# rx08-ulrich.net
KiCad netlist of a schematic drawn in EAGLE
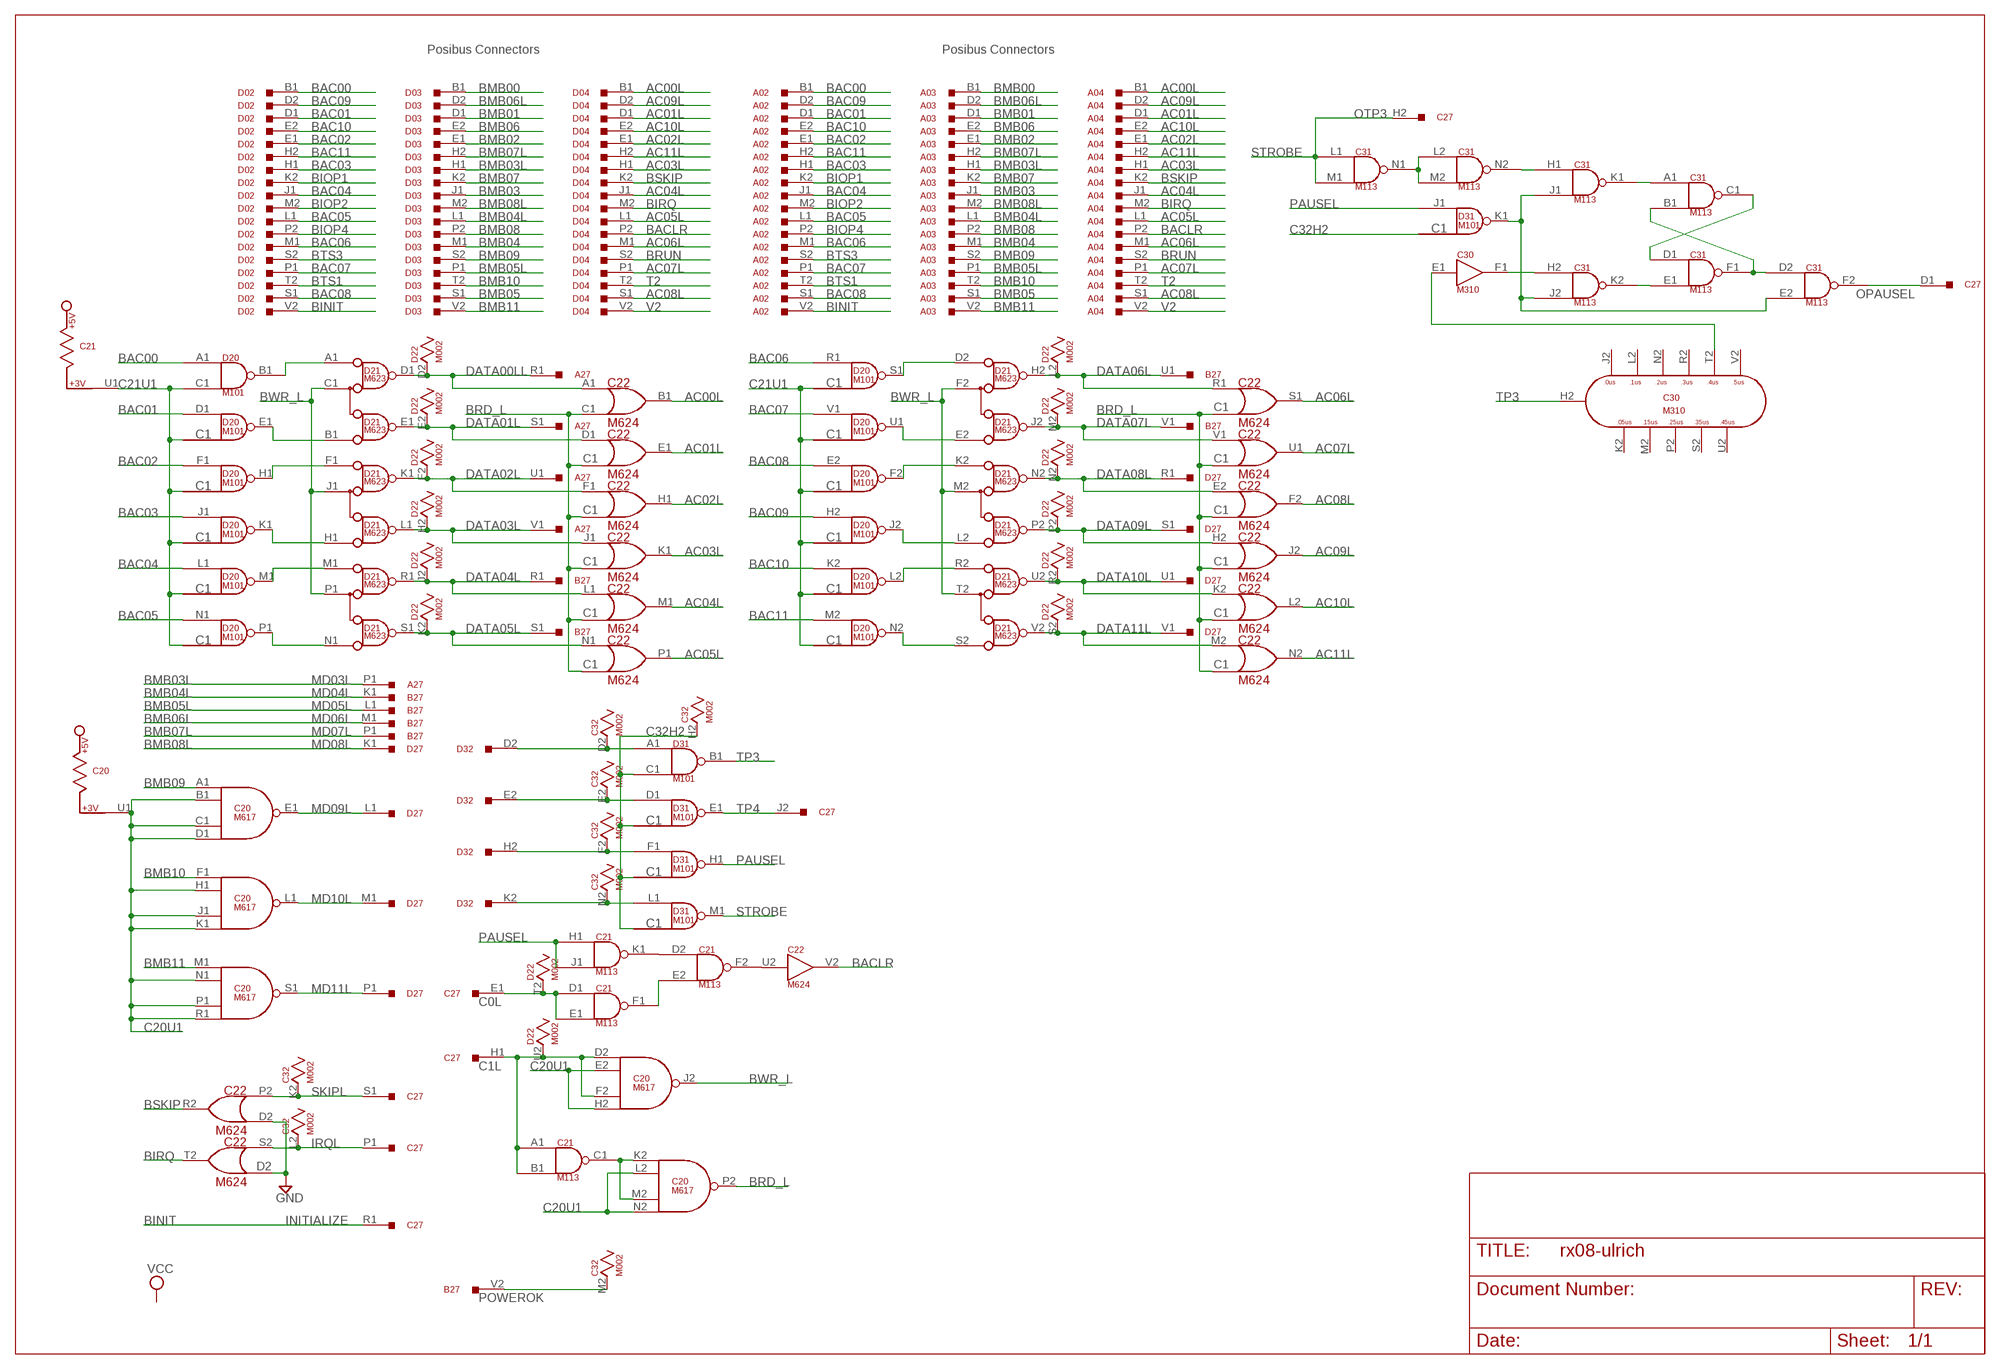
[diagram p0: schematic, sheet 1]

(export (version "E")
  (design (tool "Eeschema 10.0.6"))
  (components
    (comp (ref "A02")
      (value "M903")
      (footprint "eagle-import:H807")
      (libsource (lib "eagle-import") (part "M903"))
    )
    (comp (ref "A03")
      (value "M903")
      (footprint "eagle-import:H807")
      (libsource (lib "eagle-import") (part "M903"))
    )
    (comp (ref "A04")
      (value "M903")
      (footprint "eagle-import:H807")
      (libsource (lib "eagle-import") (part "M903"))
    )
    (comp (ref "A27")
      (value "M916")
      (footprint "eagle-import:H807")
      (libsource (lib "eagle-import") (part "M916"))
    )
    (comp (ref "B27")
      (value "M916")
      (footprint "eagle-import:H807")
      (libsource (lib "eagle-import") (part "M916"))
    )
    (comp (ref "C20")
      (value "M617")
      (footprint "eagle-import:H807")
      (libsource (lib "eagle-import") (part "M617"))
    )
    (comp (ref "C21")
      (value "M113")
      (footprint "eagle-import:H807")
      (libsource (lib "eagle-import") (part "M113"))
    )
    (comp (ref "C22")
      (value "M624")
      (footprint "eagle-import:H807")
      (libsource (lib "eagle-import") (part "M624"))
    )
    (comp (ref "C27")
      (value "M916")
      (footprint "eagle-import:H807")
      (libsource (lib "eagle-import") (part "M916"))
    )
    (comp (ref "C30")
      (value "M310")
      (footprint "eagle-import:H807")
      (libsource (lib "eagle-import") (part "M310"))
    )
    (comp (ref "C31")
      (value "M113")
      (footprint "eagle-import:H807")
      (libsource (lib "eagle-import") (part "M113"))
    )
    (comp (ref "C32")
      (value "M002")
      (footprint "eagle-import:H807")
      (libsource (lib "eagle-import") (part "M002"))
    )
    (comp (ref "D02")
      (value "M903")
      (footprint "eagle-import:H807")
      (libsource (lib "eagle-import") (part "M903"))
    )
    (comp (ref "D03")
      (value "M903")
      (footprint "eagle-import:H807")
      (libsource (lib "eagle-import") (part "M903"))
    )
    (comp (ref "D04")
      (value "M903")
      (footprint "eagle-import:H807")
      (libsource (lib "eagle-import") (part "M903"))
    )
    (comp (ref "D20")
      (value "M101")
      (footprint "eagle-import:H807")
      (libsource (lib "eagle-import") (part "M101"))
    )
    (comp (ref "D21")
      (value "M623")
      (footprint "eagle-import:H807")
      (libsource (lib "eagle-import") (part "M623"))
    )
    (comp (ref "D22")
      (value "M002")
      (footprint "eagle-import:H807")
      (libsource (lib "eagle-import") (part "M002"))
    )
    (comp (ref "D27")
      (value "M916")
      (footprint "eagle-import:H807")
      (libsource (lib "eagle-import") (part "M916"))
    )
    (comp (ref "D31")
      (value "M101")
      (footprint "eagle-import:H807")
      (libsource (lib "eagle-import") (part "M101"))
    )
    (comp (ref "D32")
      (value "M903")
      (footprint "eagle-import:H807")
      (libsource (lib "eagle-import") (part "M903"))
    )
  )
  (nets
    (net (code "1") (name "/AC00L") (class "Default")
      (node (ref "A04") (pin "B1") (pinfunction "P$2_B1") (pintype "bidirectional"))
      (node (ref "C22") (pin "B1") (pinfunction "OUT_B1") (pintype "output"))
      (node (ref "D04") (pin "B1") (pinfunction "P$2_B1") (pintype "bidirectional"))
    )
    (net (code "2") (name "/AC01L") (class "Default")
      (node (ref "A04") (pin "D1") (pinfunction "P$2_D1") (pintype "bidirectional"))
      (node (ref "C22") (pin "E1") (pinfunction "OUT_E1") (pintype "output"))
      (node (ref "D04") (pin "D1") (pinfunction "P$2_D1") (pintype "bidirectional"))
    )
    (net (code "3") (name "/AC02L") (class "Default")
      (node (ref "A04") (pin "E1") (pinfunction "P$2_E1") (pintype "bidirectional"))
      (node (ref "C22") (pin "H1") (pinfunction "OUT_H1") (pintype "output"))
      (node (ref "D04") (pin "E1") (pinfunction "P$2_E1") (pintype "bidirectional"))
    )
    (net (code "4") (name "/AC03L") (class "Default")
      (node (ref "A04") (pin "H1") (pinfunction "P$2_H1") (pintype "bidirectional"))
      (node (ref "C22") (pin "K1") (pinfunction "OUT_K1") (pintype "output"))
      (node (ref "D04") (pin "H1") (pinfunction "P$2_H1") (pintype "bidirectional"))
    )
    (net (code "5") (name "/AC04L") (class "Default")
      (node (ref "A04") (pin "J1") (pinfunction "P$2_J1") (pintype "bidirectional"))
      (node (ref "C22") (pin "M1") (pinfunction "OUT_M1") (pintype "output"))
      (node (ref "D04") (pin "J1") (pinfunction "P$2_J1") (pintype "bidirectional"))
    )
    (net (code "6") (name "/AC05L") (class "Default")
      (node (ref "A04") (pin "L1") (pinfunction "P$2_L1") (pintype "bidirectional"))
      (node (ref "C22") (pin "P1") (pinfunction "OUT_P1") (pintype "output"))
      (node (ref "D04") (pin "L1") (pinfunction "P$2_L1") (pintype "bidirectional"))
    )
    (net (code "7") (name "/AC06L") (class "Default")
      (node (ref "A04") (pin "M1") (pinfunction "P$2_M1") (pintype "bidirectional"))
      (node (ref "C22") (pin "S1") (pinfunction "OUT_S1") (pintype "output"))
      (node (ref "D04") (pin "M1") (pinfunction "P$2_M1") (pintype "bidirectional"))
    )
    (net (code "8") (name "/AC07L") (class "Default")
      (node (ref "A04") (pin "P1") (pinfunction "P$2_P1") (pintype "bidirectional"))
      (node (ref "C22") (pin "U1") (pinfunction "OUT_U1") (pintype "output"))
      (node (ref "D04") (pin "P1") (pinfunction "P$2_P1") (pintype "bidirectional"))
    )
    (net (code "9") (name "/AC08L") (class "Default")
      (node (ref "A04") (pin "S1") (pinfunction "P$2_S1") (pintype "bidirectional"))
      (node (ref "C22") (pin "F2") (pinfunction "OUT_F2") (pintype "output"))
      (node (ref "D04") (pin "S1") (pinfunction "P$2_S1") (pintype "bidirectional"))
    )
    (net (code "10") (name "/AC09L") (class "Default")
      (node (ref "A04") (pin "D2") (pinfunction "P$2_D2") (pintype "bidirectional"))
      (node (ref "C22") (pin "J2") (pinfunction "OUT_J2") (pintype "output"))
      (node (ref "D04") (pin "D2") (pinfunction "P$2_D2") (pintype "bidirectional"))
    )
    (net (code "11") (name "/AC10L") (class "Default")
      (node (ref "A04") (pin "E2") (pinfunction "P$2_E2") (pintype "bidirectional"))
      (node (ref "C22") (pin "L2") (pinfunction "OUT_L2") (pintype "output"))
      (node (ref "D04") (pin "E2") (pinfunction "P$2_E2") (pintype "bidirectional"))
    )
    (net (code "12") (name "/AC11L") (class "Default")
      (node (ref "A04") (pin "H2") (pinfunction "P$2_H2") (pintype "bidirectional"))
      (node (ref "C22") (pin "N2") (pinfunction "OUT_N2") (pintype "output"))
      (node (ref "D04") (pin "H2") (pinfunction "P$2_H2") (pintype "bidirectional"))
    )
    (net (code "13") (name "/BAC00") (class "Default")
      (node (ref "A02") (pin "B1") (pinfunction "P$2_B1") (pintype "bidirectional"))
      (node (ref "D02") (pin "B1") (pinfunction "P$2_B1") (pintype "bidirectional"))
      (node (ref "D20") (pin "A1") (pinfunction "IN1_A1") (pintype "input"))
    )
    (net (code "14") (name "/BAC01") (class "Default")
      (node (ref "A02") (pin "D1") (pinfunction "P$2_D1") (pintype "bidirectional"))
      (node (ref "D02") (pin "D1") (pinfunction "P$2_D1") (pintype "bidirectional"))
      (node (ref "D20") (pin "D1") (pinfunction "IN_D1") (pintype "input"))
    )
    (net (code "15") (name "/BAC02") (class "Default")
      (node (ref "A02") (pin "E1") (pinfunction "P$2_E1") (pintype "bidirectional"))
      (node (ref "D02") (pin "E1") (pinfunction "P$2_E1") (pintype "bidirectional"))
      (node (ref "D20") (pin "F1") (pinfunction "IN_F1") (pintype "input"))
    )
    (net (code "16") (name "/BAC03") (class "Default")
      (node (ref "A02") (pin "H1") (pinfunction "P$2_H1") (pintype "bidirectional"))
      (node (ref "D02") (pin "H1") (pinfunction "P$2_H1") (pintype "bidirectional"))
      (node (ref "D20") (pin "J1") (pinfunction "IN_J1") (pintype "input"))
    )
    (net (code "17") (name "/BAC04") (class "Default")
      (node (ref "A02") (pin "J1") (pinfunction "P$2_J1") (pintype "bidirectional"))
      (node (ref "D02") (pin "J1") (pinfunction "P$2_J1") (pintype "bidirectional"))
      (node (ref "D20") (pin "L1") (pinfunction "IN_L1") (pintype "input"))
    )
    (net (code "18") (name "/BAC05") (class "Default")
      (node (ref "A02") (pin "L1") (pinfunction "P$2_L1") (pintype "bidirectional"))
      (node (ref "D02") (pin "L1") (pinfunction "P$2_L1") (pintype "bidirectional"))
      (node (ref "D20") (pin "N1") (pinfunction "IN_N1") (pintype "input"))
    )
    (net (code "19") (name "/BAC06") (class "Default")
      (node (ref "A02") (pin "M1") (pinfunction "P$2_M1") (pintype "bidirectional"))
      (node (ref "D02") (pin "M1") (pinfunction "P$2_M1") (pintype "bidirectional"))
      (node (ref "D20") (pin "R1") (pinfunction "IN_R1") (pintype "input"))
    )
    (net (code "20") (name "/BAC07") (class "Default")
      (node (ref "A02") (pin "P1") (pinfunction "P$2_P1") (pintype "bidirectional"))
      (node (ref "D02") (pin "P1") (pinfunction "P$2_P1") (pintype "bidirectional"))
      (node (ref "D20") (pin "V1") (pinfunction "IN_V1") (pintype "input"))
    )
    (net (code "21") (name "/BAC08") (class "Default")
      (node (ref "A02") (pin "S1") (pinfunction "P$2_S1") (pintype "bidirectional"))
      (node (ref "D02") (pin "S1") (pinfunction "P$2_S1") (pintype "bidirectional"))
      (node (ref "D20") (pin "E2") (pinfunction "IN_E2") (pintype "input"))
    )
    (net (code "22") (name "/BAC09") (class "Default")
      (node (ref "A02") (pin "D2") (pinfunction "P$2_D2") (pintype "bidirectional"))
      (node (ref "D02") (pin "D2") (pinfunction "P$2_D2") (pintype "bidirectional"))
      (node (ref "D20") (pin "H2") (pinfunction "IN_H2") (pintype "input"))
    )
    (net (code "23") (name "/BAC10") (class "Default")
      (node (ref "A02") (pin "E2") (pinfunction "P$2_E2") (pintype "bidirectional"))
      (node (ref "D02") (pin "E2") (pinfunction "P$2_E2") (pintype "bidirectional"))
      (node (ref "D20") (pin "K2") (pinfunction "IN_K2") (pintype "input"))
    )
    (net (code "24") (name "/BAC11") (class "Default")
      (node (ref "A02") (pin "H2") (pinfunction "P$2_H2") (pintype "bidirectional"))
      (node (ref "D02") (pin "H2") (pinfunction "P$2_H2") (pintype "bidirectional"))
      (node (ref "D20") (pin "M2") (pinfunction "IN_M2") (pintype "input"))
    )
    (net (code "25") (name "/BACLR") (class "Default")
      (node (ref "A04") (pin "P2") (pinfunction "P$2_P2") (pintype "bidirectional"))
      (node (ref "C22") (pin "V2") (pinfunction "OUT_V2") (pintype "output"))
      (node (ref "D04") (pin "P2") (pinfunction "P$2_P2") (pintype "bidirectional"))
    )
    (net (code "26") (name "/BINIT") (class "Default")
      (node (ref "A02") (pin "V2") (pinfunction "P$2_V2") (pintype "bidirectional"))
      (node (ref "C27") (pin "R1") (pinfunction "P$2_R1") (pintype "bidirectional"))
      (node (ref "D02") (pin "V2") (pinfunction "P$2_V2") (pintype "bidirectional"))
    )
    (net (code "27") (name "/BIOP1") (class "Default")
      (node (ref "A02") (pin "K2") (pinfunction "P$2_K2") (pintype "bidirectional"))
      (node (ref "D02") (pin "K2") (pinfunction "P$2_K2") (pintype "bidirectional"))
    )
    (net (code "28") (name "/BIOP2") (class "Default")
      (node (ref "A02") (pin "M2") (pinfunction "P$2_M2") (pintype "bidirectional"))
      (node (ref "D02") (pin "M2") (pinfunction "P$2_M2") (pintype "bidirectional"))
    )
    (net (code "29") (name "/BIOP4") (class "Default")
      (node (ref "A02") (pin "P2") (pinfunction "P$2_P2") (pintype "bidirectional"))
      (node (ref "D02") (pin "P2") (pinfunction "P$2_P2") (pintype "bidirectional"))
    )
    (net (code "30") (name "/BIRQ") (class "Default")
      (node (ref "A04") (pin "M2") (pinfunction "P$2_M2") (pintype "bidirectional"))
      (node (ref "C22") (pin "T2") (pinfunction "OUT_T2") (pintype "output"))
      (node (ref "D04") (pin "M2") (pinfunction "P$2_M2") (pintype "bidirectional"))
    )
    (net (code "31") (name "/BMB00") (class "Default")
      (node (ref "A03") (pin "B1") (pinfunction "P$2_B1") (pintype "bidirectional"))
      (node (ref "D03") (pin "B1") (pinfunction "P$2_B1") (pintype "bidirectional"))
    )
    (net (code "32") (name "/BMB01") (class "Default")
      (node (ref "A03") (pin "D1") (pinfunction "P$2_D1") (pintype "bidirectional"))
      (node (ref "D03") (pin "D1") (pinfunction "P$2_D1") (pintype "bidirectional"))
    )
    (net (code "33") (name "/BMB02") (class "Default")
      (node (ref "A03") (pin "E1") (pinfunction "P$2_E1") (pintype "bidirectional"))
      (node (ref "D03") (pin "E1") (pinfunction "P$2_E1") (pintype "bidirectional"))
    )
    (net (code "34") (name "/BMB03") (class "Default")
      (node (ref "A03") (pin "J1") (pinfunction "P$2_J1") (pintype "bidirectional"))
      (node (ref "D03") (pin "J1") (pinfunction "P$2_J1") (pintype "bidirectional"))
    )
    (net (code "35") (name "/BMB03L") (class "Default")
      (node (ref "A03") (pin "H1") (pinfunction "P$2_H1") (pintype "bidirectional"))
      (node (ref "A27") (pin "P1") (pinfunction "P$2_P1") (pintype "bidirectional"))
      (node (ref "D03") (pin "H1") (pinfunction "P$2_H1") (pintype "bidirectional"))
    )
    (net (code "36") (name "/BMB04") (class "Default")
      (node (ref "A03") (pin "M1") (pinfunction "P$2_M1") (pintype "bidirectional"))
      (node (ref "D03") (pin "M1") (pinfunction "P$2_M1") (pintype "bidirectional"))
    )
    (net (code "37") (name "/BMB04L") (class "Default")
      (node (ref "A03") (pin "L1") (pinfunction "P$2_L1") (pintype "bidirectional"))
      (node (ref "B27") (pin "K1") (pinfunction "P$2_K1") (pintype "bidirectional"))
      (node (ref "D03") (pin "L1") (pinfunction "P$2_L1") (pintype "bidirectional"))
    )
    (net (code "38") (name "/BMB05") (class "Default")
      (node (ref "A03") (pin "S1") (pinfunction "P$2_S1") (pintype "bidirectional"))
      (node (ref "D03") (pin "S1") (pinfunction "P$2_S1") (pintype "bidirectional"))
    )
    (net (code "39") (name "/BMB05L") (class "Default")
      (node (ref "A03") (pin "P1") (pinfunction "P$2_P1") (pintype "bidirectional"))
      (node (ref "B27") (pin "L1") (pinfunction "P$2_L1") (pintype "bidirectional"))
      (node (ref "D03") (pin "P1") (pinfunction "P$2_P1") (pintype "bidirectional"))
    )
    (net (code "40") (name "/BMB06") (class "Default")
      (node (ref "A03") (pin "E2") (pinfunction "P$2_E2") (pintype "bidirectional"))
      (node (ref "D03") (pin "E2") (pinfunction "P$2_E2") (pintype "bidirectional"))
    )
    (net (code "41") (name "/BMB06L") (class "Default")
      (node (ref "A03") (pin "D2") (pinfunction "P$2_D2") (pintype "bidirectional"))
      (node (ref "B27") (pin "M1") (pinfunction "P$2_M1") (pintype "bidirectional"))
      (node (ref "D03") (pin "D2") (pinfunction "P$2_D2") (pintype "bidirectional"))
    )
    (net (code "42") (name "/BMB07") (class "Default")
      (node (ref "A03") (pin "K2") (pinfunction "P$2_K2") (pintype "bidirectional"))
      (node (ref "D03") (pin "K2") (pinfunction "P$2_K2") (pintype "bidirectional"))
    )
    (net (code "43") (name "/BMB07L") (class "Default")
      (node (ref "A03") (pin "H2") (pinfunction "P$2_H2") (pintype "bidirectional"))
      (node (ref "B27") (pin "P1") (pinfunction "P$2_P1") (pintype "bidirectional"))
      (node (ref "D03") (pin "H2") (pinfunction "P$2_H2") (pintype "bidirectional"))
    )
    (net (code "44") (name "/BMB08") (class "Default")
      (node (ref "A03") (pin "P2") (pinfunction "P$2_P2") (pintype "bidirectional"))
      (node (ref "D03") (pin "P2") (pinfunction "P$2_P2") (pintype "bidirectional"))
    )
    (net (code "45") (name "/BMB08L") (class "Default")
      (node (ref "A03") (pin "M2") (pinfunction "P$2_M2") (pintype "bidirectional"))
      (node (ref "D03") (pin "M2") (pinfunction "P$2_M2") (pintype "bidirectional"))
      (node (ref "D27") (pin "K1") (pinfunction "P$2_K1") (pintype "bidirectional"))
    )
    (net (code "46") (name "/BMB09") (class "Default")
      (node (ref "A03") (pin "S2") (pinfunction "P$2_S2") (pintype "bidirectional"))
      (node (ref "C20") (pin "A1") (pinfunction "IN1_A1") (pintype "input"))
      (node (ref "D03") (pin "S2") (pinfunction "P$2_S2") (pintype "bidirectional"))
    )
    (net (code "47") (name "/BMB10") (class "Default")
      (node (ref "A03") (pin "T2") (pinfunction "P$2_T2") (pintype "bidirectional"))
      (node (ref "C20") (pin "F1") (pinfunction "IN1_F1") (pintype "input"))
      (node (ref "D03") (pin "T2") (pinfunction "P$2_T2") (pintype "bidirectional"))
    )
    (net (code "48") (name "/BMB11") (class "Default")
      (node (ref "A03") (pin "V2") (pinfunction "P$2_V2") (pintype "bidirectional"))
      (node (ref "C20") (pin "M1") (pinfunction "IN1_M1") (pintype "input"))
      (node (ref "D03") (pin "V2") (pinfunction "P$2_V2") (pintype "bidirectional"))
    )
    (net (code "49") (name "/BRD_L") (class "Default")
      (node (ref "C20") (pin "P2") (pinfunction "OUT_P2") (pintype "open_collector"))
      (node (ref "C22") (pin "C1") (pinfunction "IN2_C1") (pintype "input"))
    )
    (net (code "50") (name "/BRUN") (class "Default")
      (node (ref "A04") (pin "S2") (pinfunction "P$2_S2") (pintype "bidirectional"))
      (node (ref "D04") (pin "S2") (pinfunction "P$2_S2") (pintype "bidirectional"))
    )
    (net (code "51") (name "/BSKIP") (class "Default")
      (node (ref "A04") (pin "K2") (pinfunction "P$2_K2") (pintype "bidirectional"))
      (node (ref "C22") (pin "R2") (pinfunction "OUT_R2") (pintype "output"))
      (node (ref "D04") (pin "K2") (pinfunction "P$2_K2") (pintype "bidirectional"))
    )
    (net (code "52") (name "/BTS1") (class "Default")
      (node (ref "A02") (pin "T2") (pinfunction "P$2_T2") (pintype "bidirectional"))
      (node (ref "D02") (pin "T2") (pinfunction "P$2_T2") (pintype "bidirectional"))
    )
    (net (code "53") (name "/BTS3") (class "Default")
      (node (ref "A02") (pin "S2") (pinfunction "P$2_S2") (pintype "bidirectional"))
      (node (ref "D02") (pin "S2") (pinfunction "P$2_S2") (pintype "bidirectional"))
    )
    (net (code "54") (name "/BWR_L") (class "Default")
      (node (ref "C20") (pin "J2") (pinfunction "OUT_J2") (pintype "open_collector"))
      (node (ref "D21") (pin "C1") (pinfunction "C_C1") (pintype "input"))
      (node (ref "D21") (pin "F2") (pinfunction "C_F2") (pintype "input"))
      (node (ref "D21") (pin "J1") (pinfunction "C_J1") (pintype "input"))
      (node (ref "D21") (pin "M2") (pinfunction "C_M2") (pintype "input"))
      (node (ref "D21") (pin "P1") (pinfunction "C_P1") (pintype "input"))
      (node (ref "D21") (pin "T2") (pinfunction "C_T2") (pintype "input"))
    )
    (net (code "55") (name "/C0L") (class "Default")
      (node (ref "C21") (pin "D1") (pinfunction "IN1_D1") (pintype "input"))
      (node (ref "C21") (pin "E1") (pinfunction "IN2_E1") (pintype "input"))
      (node (ref "C27") (pin "E1") (pinfunction "P$2_E1") (pintype "bidirectional"))
      (node (ref "D22") (pin "T2") (pinfunction "P$1_T2") (pintype "passive"))
    )
    (net (code "56") (name "/C1L") (class "Default")
      (node (ref "C20") (pin "D2") (pinfunction "IN1_D2") (pintype "input"))
      (node (ref "C20") (pin "F2") (pinfunction "IN3_F2") (pintype "input"))
      (node (ref "C21") (pin "A1") (pinfunction "IN1_A1") (pintype "input"))
      (node (ref "C21") (pin "B1") (pinfunction "IN2_B1") (pintype "input"))
      (node (ref "C27") (pin "H1") (pinfunction "P$2_H1") (pintype "bidirectional"))
      (node (ref "D22") (pin "U2") (pinfunction "P$1_U2") (pintype "passive"))
    )
    (net (code "57") (name "/C20U1") (class "Default")
      (node (ref "C20") (pin "B1") (pinfunction "IN2_B1") (pintype "input"))
      (node (ref "C20") (pin "C1") (pinfunction "IN3_C1") (pintype "input"))
      (node (ref "C20") (pin "D1") (pinfunction "IN4_D1") (pintype "input"))
      (node (ref "C20") (pin "E2") (pinfunction "IN2_E2") (pintype "input"))
      (node (ref "C20") (pin "H1") (pinfunction "IN2_H1") (pintype "input"))
      (node (ref "C20") (pin "H2") (pinfunction "IN4_H2") (pintype "input"))
      (node (ref "C20") (pin "J1") (pinfunction "IN3_J1") (pintype "input"))
      (node (ref "C20") (pin "K1") (pinfunction "IN4_K1") (pintype "input"))
      (node (ref "C20") (pin "L2") (pinfunction "IN2_L2") (pintype "input"))
      (node (ref "C20") (pin "N1") (pinfunction "IN2_N1") (pintype "input"))
      (node (ref "C20") (pin "N2") (pinfunction "IN4_N2") (pintype "input"))
      (node (ref "C20") (pin "P1") (pinfunction "IN3_P1") (pintype "input"))
      (node (ref "C20") (pin "R1") (pinfunction "IN4_R1") (pintype "input"))
      (node (ref "C20") (pin "U1") (pinfunction "P$1_U1") (pintype "passive"))
    )
    (net (code "58") (name "/C21U1") (class "Default")
      (node (ref "C21") (pin "U1") (pinfunction "P$1_U1") (pintype "passive"))
      (node (ref "D20") (pin "C1") (pinfunction "IN2_C1") (pintype "input"))
    )
    (net (code "59") (name "/C32H2") (class "Default")
      (node (ref "C32") (pin "H2") (pinfunction "P$1_H2") (pintype "passive"))
      (node (ref "D31") (pin "C1") (pinfunction "IN2_C1") (pintype "input"))
    )
    (net (code "60") (name "/DATA00LL") (class "Default")
      (node (ref "A27") (pin "R1") (pinfunction "P$2_R1") (pintype "bidirectional"))
      (node (ref "C22") (pin "A1") (pinfunction "IN1_A1") (pintype "input"))
      (node (ref "D21") (pin "D1") (pinfunction "D_D1") (pintype "open_collector"))
      (node (ref "D22") (pin "D2") (pinfunction "P$1_D2") (pintype "passive"))
    )
    (net (code "61") (name "/DATA01L") (class "Default")
      (node (ref "A27") (pin "S1") (pinfunction "P$2_S1") (pintype "bidirectional"))
      (node (ref "C22") (pin "D1") (pinfunction "IN_D1") (pintype "input"))
      (node (ref "D21") (pin "E1") (pinfunction "E_E1") (pintype "open_collector"))
      (node (ref "D22") (pin "E2") (pinfunction "P$1_E2") (pintype "passive"))
    )
    (net (code "62") (name "/DATA02L") (class "Default")
      (node (ref "A27") (pin "U1") (pinfunction "P$2_U1") (pintype "bidirectional"))
      (node (ref "C22") (pin "F1") (pinfunction "IN_F1") (pintype "input"))
      (node (ref "D21") (pin "K1") (pinfunction "D_K1") (pintype "open_collector"))
      (node (ref "D22") (pin "F2") (pinfunction "P$1_F2") (pintype "passive"))
    )
    (net (code "63") (name "/DATA03L") (class "Default")
      (node (ref "A27") (pin "V1") (pinfunction "P$2_V1") (pintype "bidirectional"))
      (node (ref "C22") (pin "J1") (pinfunction "IN_J1") (pintype "input"))
      (node (ref "D21") (pin "L1") (pinfunction "E_L1") (pintype "open_collector"))
      (node (ref "D22") (pin "H2") (pinfunction "P$1_H2") (pintype "passive"))
    )
    (net (code "64") (name "/DATA04L") (class "Default")
      (node (ref "B27") (pin "R1") (pinfunction "P$2_R1") (pintype "bidirectional"))
      (node (ref "C22") (pin "L1") (pinfunction "IN_L1") (pintype "input"))
      (node (ref "D21") (pin "R1") (pinfunction "D_R1") (pintype "open_collector"))
      (node (ref "D22") (pin "J2") (pinfunction "P$1_J2") (pintype "passive"))
    )
    (net (code "65") (name "/DATA05L") (class "Default")
      (node (ref "B27") (pin "S1") (pinfunction "P$2_S1") (pintype "bidirectional"))
      (node (ref "C22") (pin "N1") (pinfunction "IN_N1") (pintype "input"))
      (node (ref "D21") (pin "S1") (pinfunction "E_S1") (pintype "open_collector"))
      (node (ref "D22") (pin "K2") (pinfunction "P$1_K2") (pintype "passive"))
    )
    (net (code "66") (name "/DATA06L") (class "Default")
      (node (ref "B27") (pin "U1") (pinfunction "P$2_U1") (pintype "bidirectional"))
      (node (ref "C22") (pin "R1") (pinfunction "IN_R1") (pintype "input"))
      (node (ref "D21") (pin "H2") (pinfunction "D_H2") (pintype "open_collector"))
      (node (ref "D22") (pin "L2") (pinfunction "P$1_L2") (pintype "passive"))
    )
    (net (code "67") (name "/DATA07L") (class "Default")
      (node (ref "B27") (pin "V1") (pinfunction "P$2_V1") (pintype "bidirectional"))
      (node (ref "C22") (pin "V1") (pinfunction "IN_V1") (pintype "input"))
      (node (ref "D21") (pin "J2") (pinfunction "E_J2") (pintype "open_collector"))
      (node (ref "D22") (pin "M2") (pinfunction "P$1_M2") (pintype "passive"))
    )
    (net (code "68") (name "/DATA08L") (class "Default")
      (node (ref "C22") (pin "E2") (pinfunction "IN_E2") (pintype "input"))
      (node (ref "D21") (pin "N2") (pinfunction "D_N2") (pintype "open_collector"))
      (node (ref "D22") (pin "N2") (pinfunction "P$1_N2") (pintype "passive"))
      (node (ref "D27") (pin "R1") (pinfunction "P$2_R1") (pintype "bidirectional"))
    )
    (net (code "69") (name "/DATA09L") (class "Default")
      (node (ref "C22") (pin "H2") (pinfunction "IN_H2") (pintype "input"))
      (node (ref "D21") (pin "P2") (pinfunction "E_P2") (pintype "open_collector"))
      (node (ref "D22") (pin "P2") (pinfunction "P$1_P2") (pintype "passive"))
      (node (ref "D27") (pin "S1") (pinfunction "P$2_S1") (pintype "bidirectional"))
    )
    (net (code "70") (name "/DATA10L") (class "Default")
      (node (ref "C22") (pin "K2") (pinfunction "IN_K2") (pintype "input"))
      (node (ref "D21") (pin "U2") (pinfunction "D_U2") (pintype "open_collector"))
      (node (ref "D22") (pin "R2") (pinfunction "P$1_R2") (pintype "passive"))
      (node (ref "D27") (pin "U1") (pinfunction "P$2_U1") (pintype "bidirectional"))
    )
    (net (code "71") (name "/DATA11L") (class "Default")
      (node (ref "C22") (pin "M2") (pinfunction "IN_M2") (pintype "input"))
      (node (ref "D21") (pin "V2") (pinfunction "E_V2") (pintype "open_collector"))
      (node (ref "D22") (pin "S2") (pinfunction "P$1_S2") (pintype "passive"))
      (node (ref "D27") (pin "V1") (pinfunction "P$2_V1") (pintype "bidirectional"))
    )
    (net (code "72") (name "/IRQL") (class "Default")
      (node (ref "C22") (pin "S2") (pinfunction "IN_S2") (pintype "input"))
      (node (ref "C27") (pin "P1") (pinfunction "P$2_P1") (pintype "bidirectional"))
      (node (ref "C32") (pin "L2") (pinfunction "P$1_L2") (pintype "passive"))
    )
    (net (code "73") (name "/MD09L") (class "Default")
      (node (ref "C20") (pin "E1") (pinfunction "OUT_E1") (pintype "open_collector"))
      (node (ref "D27") (pin "L1") (pinfunction "P$2_L1") (pintype "bidirectional"))
    )
    (net (code "74") (name "/MD10L") (class "Default")
      (node (ref "C20") (pin "L1") (pinfunction "OUT_L1") (pintype "open_collector"))
      (node (ref "D27") (pin "M1") (pinfunction "P$2_M1") (pintype "bidirectional"))
    )
    (net (code "75") (name "/MD11L") (class "Default")
      (node (ref "C20") (pin "S1") (pinfunction "OUT_S1") (pintype "open_collector"))
      (node (ref "D27") (pin "P1") (pinfunction "P$2_P1") (pintype "bidirectional"))
    )
    (net (code "76") (name "/OPAUSEL") (class "Default")
      (node (ref "C27") (pin "D1") (pinfunction "P$2_D1") (pintype "bidirectional"))
      (node (ref "C31") (pin "F2") (pinfunction "OUT_F2") (pintype "output"))
    )
    (net (code "77") (name "/PAUSEL") (class "Default")
      (node (ref "C21") (pin "H1") (pinfunction "IN1_H1") (pintype "input"))
      (node (ref "C21") (pin "J1") (pinfunction "IN2_J1") (pintype "input"))
      (node (ref "D31") (pin "H1") (pinfunction "OUT_H1") (pintype "output"))
      (node (ref "D31") (pin "J1") (pinfunction "IN_J1") (pintype "input"))
    )
    (net (code "78") (name "/POWEROK") (class "Default")
      (node (ref "B27") (pin "V2") (pinfunction "P$2_V2") (pintype "bidirectional"))
      (node (ref "C32") (pin "M2") (pinfunction "P$1_M2") (pintype "passive"))
    )
    (net (code "79") (name "/SKIPL") (class "Default")
      (node (ref "C22") (pin "P2") (pinfunction "IN1_P2") (pintype "input"))
      (node (ref "C27") (pin "S1") (pinfunction "P$2_S1") (pintype "bidirectional"))
      (node (ref "C32") (pin "K2") (pinfunction "P$1_K2") (pintype "passive"))
    )
    (net (code "80") (name "/STROBE") (class "Default")
      (node (ref "C27") (pin "H2") (pinfunction "P$2_H2") (pintype "bidirectional"))
      (node (ref "C31") (pin "L1") (pinfunction "IN1_L1") (pintype "input"))
      (node (ref "C31") (pin "M1") (pinfunction "IN2_M1") (pintype "input"))
      (node (ref "D31") (pin "M1") (pinfunction "OUT_M1") (pintype "output"))
    )
    (net (code "81") (name "/T2") (class "Default")
      (node (ref "A04") (pin "T2") (pinfunction "P$2_T2") (pintype "bidirectional"))
      (node (ref "D04") (pin "T2") (pinfunction "P$2_T2") (pintype "bidirectional"))
    )
    (net (code "82") (name "/TP3") (class "Default")
      (node (ref "C30") (pin "H2") (pinfunction "H2_H2") (pintype "input"))
      (node (ref "D31") (pin "B1") (pinfunction "OUT_B1") (pintype "output"))
    )
    (net (code "83") (name "/TP4") (class "Default")
      (node (ref "C27") (pin "J2") (pinfunction "P$2_J2") (pintype "bidirectional"))
      (node (ref "D31") (pin "E1") (pinfunction "OUT_E1") (pintype "output"))
    )
    (net (code "84") (name "/V2") (class "Default")
      (node (ref "A04") (pin "V2") (pinfunction "P$2_V2") (pintype "bidirectional"))
      (node (ref "D04") (pin "V2") (pinfunction "P$2_V2") (pintype "bidirectional"))
    )
    (net (code "85") (name "GND") (class "Default")
      (node (ref "C22") (pin "D2") (pinfunction "IN2_D2") (pintype "input"))
    )
    (net (code "86") (name "Net-(C20F-IN1)") (class "Default")
      (node (ref "C20") (pin "K2") (pinfunction "IN1_K2") (pintype "input"))
      (node (ref "C20") (pin "M2") (pinfunction "IN3_M2") (pintype "input"))
      (node (ref "C21") (pin "C1") (pinfunction "OUT_C1") (pintype "output"))
    )
    (net (code "87") (name "Net-(C21B-OUT)") (class "Default")
      (node (ref "C21") (pin "E2") (pinfunction "IN2_E2") (pintype "input"))
      (node (ref "C21") (pin "F1") (pinfunction "OUT_F1") (pintype "output"))
    )
    (net (code "88") (name "Net-(C21C-IN1)") (class "Default")
      (node (ref "C21") (pin "D2") (pinfunction "IN1_D2") (pintype "input"))
      (node (ref "C21") (pin "K1") (pinfunction "OUT_K1") (pintype "output"))
    )
    (net (code "89") (name "Net-(C21C-OUT)") (class "Default")
      (node (ref "C21") (pin "F2") (pinfunction "OUT_F2") (pintype "output"))
      (node (ref "C22") (pin "U2") (pinfunction "IN_U2") (pintype "input"))
    )
    (net (code "90") (name "Net-(C30A-IN)") (class "Default")
      (node (ref "C30") (pin "E1") (pinfunction "IN_E1") (pintype "input"))
      (node (ref "C30") (pin "T2") (pinfunction "T2_T2") (pintype "output"))
    )
    (net (code "91") (name "Net-(C30A-OUT)") (class "Default")
      (node (ref "C30") (pin "F1") (pinfunction "OUT_F1") (pintype "output"))
      (node (ref "C31") (pin "H2") (pinfunction "IN1_H2") (pintype "input"))
    )
    (net (code "92") (name "Net-(C31A-IN1)") (class "Default")
      (node (ref "C31") (pin "A1") (pinfunction "IN1_A1") (pintype "input"))
      (node (ref "C31") (pin "K1") (pinfunction "OUT_K1") (pintype "output"))
    )
    (net (code "93") (name "Net-(C31A-IN2)") (class "Default")
      (node (ref "C31") (pin "B1") (pinfunction "IN2_B1") (pintype "input"))
      (node (ref "C31") (pin "D2") (pinfunction "IN1_D2") (pintype "input"))
      (node (ref "C31") (pin "F1") (pinfunction "OUT_F1") (pintype "output"))
    )
    (net (code "94") (name "Net-(C31A-OUT)") (class "Default")
      (node (ref "C31") (pin "C1") (pinfunction "OUT_C1") (pintype "output"))
      (node (ref "C31") (pin "D1") (pinfunction "IN1_D1") (pintype "input"))
    )
    (net (code "95") (name "Net-(C31B-IN2)") (class "Default")
      (node (ref "C31") (pin "E1") (pinfunction "IN2_E1") (pintype "input"))
      (node (ref "C31") (pin "K2") (pinfunction "OUT_K2") (pintype "output"))
    )
    (net (code "96") (name "Net-(C31C-IN2)") (class "Default")
      (node (ref "C31") (pin "E2") (pinfunction "IN2_E2") (pintype "input"))
      (node (ref "C31") (pin "J1") (pinfunction "IN2_J1") (pintype "input"))
      (node (ref "C31") (pin "J2") (pinfunction "IN2_J2") (pintype "input"))
      (node (ref "D31") (pin "K1") (pinfunction "OUT_K1") (pintype "output"))
    )
    (net (code "97") (name "Net-(C31F-IN1)") (class "Default")
      (node (ref "C31") (pin "H1") (pinfunction "IN1_H1") (pintype "input"))
      (node (ref "C31") (pin "N2") (pinfunction "OUT_N2") (pintype "output"))
    )
    (net (code "98") (name "Net-(C31H-OUT)") (class "Default")
      (node (ref "C31") (pin "L2") (pinfunction "IN1_L2") (pintype "input"))
      (node (ref "C31") (pin "M2") (pinfunction "IN2_M2") (pintype "input"))
      (node (ref "C31") (pin "N1") (pinfunction "OUT_N1") (pintype "output"))
    )
    (net (code "99") (name "Net-(C32A-P$1)") (class "Default")
      (node (ref "C32") (pin "D2") (pinfunction "P$1_D2") (pintype "passive"))
      (node (ref "D31") (pin "A1") (pinfunction "IN1_A1") (pintype "input"))
      (node (ref "D32") (pin "D2") (pinfunction "P$2_D2") (pintype "bidirectional"))
    )
    (net (code "100") (name "Net-(C32B-P$1)") (class "Default")
      (node (ref "C32") (pin "E2") (pinfunction "P$1_E2") (pintype "passive"))
      (node (ref "D31") (pin "D1") (pinfunction "IN_D1") (pintype "input"))
      (node (ref "D32") (pin "E2") (pinfunction "P$2_E2") (pintype "bidirectional"))
    )
    (net (code "101") (name "Net-(C32C-P$1)") (class "Default")
      (node (ref "C32") (pin "F2") (pinfunction "P$1_F2") (pintype "passive"))
      (node (ref "D31") (pin "F1") (pinfunction "IN_F1") (pintype "input"))
      (node (ref "D32") (pin "H2") (pinfunction "P$2_H2") (pintype "bidirectional"))
    )
    (net (code "102") (name "Net-(C32J-P$1)") (class "Default")
      (node (ref "C32") (pin "N2") (pinfunction "P$1_N2") (pintype "passive"))
      (node (ref "D31") (pin "L1") (pinfunction "IN_L1") (pintype "input"))
      (node (ref "D32") (pin "K2") (pinfunction "P$2_K2") (pintype "bidirectional"))
    )
    (net (code "103") (name "Net-(D20A-OUT)") (class "Default")
      (node (ref "D20") (pin "B1") (pinfunction "OUT_B1") (pintype "output"))
      (node (ref "D21") (pin "A1") (pinfunction "A_A1") (pintype "input"))
    )
    (net (code "104") (name "Net-(D20B-OUT)") (class "Default")
      (node (ref "D20") (pin "E1") (pinfunction "OUT_E1") (pintype "output"))
      (node (ref "D21") (pin "B1") (pinfunction "B_B1") (pintype "input"))
    )
    (net (code "105") (name "Net-(D20C-OUT)") (class "Default")
      (node (ref "D20") (pin "F2") (pinfunction "OUT_F2") (pintype "output"))
      (node (ref "D21") (pin "K2") (pinfunction "A_K2") (pintype "input"))
    )
    (net (code "106") (name "Net-(D20F-OUT)") (class "Default")
      (node (ref "D20") (pin "H1") (pinfunction "OUT_H1") (pintype "output"))
      (node (ref "D21") (pin "F1") (pinfunction "A_F1") (pintype "input"))
    )
    (net (code "107") (name "Net-(D20G-OUT)") (class "Default")
      (node (ref "D20") (pin "J2") (pinfunction "OUT_J2") (pintype "output"))
      (node (ref "D21") (pin "L2") (pinfunction "B_L2") (pintype "input"))
    )
    (net (code "108") (name "Net-(D20H-OUT)") (class "Default")
      (node (ref "D20") (pin "K1") (pinfunction "OUT_K1") (pintype "output"))
      (node (ref "D21") (pin "H1") (pinfunction "B_H1") (pintype "input"))
    )
    (net (code "109") (name "Net-(D20I-OUT)") (class "Default")
      (node (ref "D20") (pin "L2") (pinfunction "OUT_L2") (pintype "output"))
      (node (ref "D21") (pin "R2") (pinfunction "A_R2") (pintype "input"))
    )
    (net (code "110") (name "Net-(D20J-OUT)") (class "Default")
      (node (ref "D20") (pin "M1") (pinfunction "OUT_M1") (pintype "output"))
      (node (ref "D21") (pin "M1") (pinfunction "A_M1") (pintype "input"))
    )
    (net (code "111") (name "Net-(D20K-OUT)") (class "Default")
      (node (ref "D20") (pin "N2") (pinfunction "OUT_N2") (pintype "output"))
      (node (ref "D21") (pin "S2") (pinfunction "B_S2") (pintype "input"))
    )
    (net (code "112") (name "Net-(D20L-OUT)") (class "Default")
      (node (ref "D20") (pin "P1") (pinfunction "OUT_P1") (pintype "output"))
      (node (ref "D21") (pin "N1") (pinfunction "B_N1") (pintype "input"))
    )
    (net (code "113") (name "Net-(D20N-OUT)") (class "Default")
      (node (ref "D20") (pin "S1") (pinfunction "OUT_S1") (pintype "output"))
      (node (ref "D21") (pin "D2") (pinfunction "A_D2") (pintype "input"))
    )
    (net (code "114") (name "Net-(D20P-OUT)") (class "Default")
      (node (ref "D20") (pin "U1") (pinfunction "OUT_U1") (pintype "output"))
      (node (ref "D21") (pin "E2") (pinfunction "B_E2") (pintype "input"))
    )
    (net (code "116") (name "unconnected-(C30-PadJ2)") (class "Default")
      (node (ref "C30") (pin "J2") (pinfunction "J2_J2") (pintype "output"))
    )
    (net (code "117") (name "unconnected-(C30-PadK2)") (class "Default")
      (node (ref "C30") (pin "K2") (pinfunction "K2_K2") (pintype "output"))
    )
    (net (code "118") (name "unconnected-(C30-PadL2)") (class "Default")
      (node (ref "C30") (pin "L2") (pinfunction "L2_L2") (pintype "output"))
    )
    (net (code "119") (name "unconnected-(C30-PadM2)") (class "Default")
      (node (ref "C30") (pin "M2") (pinfunction "M2_M2") (pintype "output"))
    )
    (net (code "120") (name "unconnected-(C30-PadN2)") (class "Default")
      (node (ref "C30") (pin "N2") (pinfunction "N2_N2") (pintype "output"))
    )
    (net (code "121") (name "unconnected-(C30-PadP2)") (class "Default")
      (node (ref "C30") (pin "P2") (pinfunction "P2_P2") (pintype "output"))
    )
    (net (code "122") (name "unconnected-(C30-PadR2)") (class "Default")
      (node (ref "C30") (pin "R2") (pinfunction "R2_R2") (pintype "output"))
    )
    (net (code "123") (name "unconnected-(C30-PadS2)") (class "Default")
      (node (ref "C30") (pin "S2") (pinfunction "S2_S2") (pintype "output"))
    )
    (net (code "124") (name "unconnected-(C30-PadU2)") (class "Default")
      (node (ref "C30") (pin "U2") (pinfunction "U2_U2") (pintype "output"))
    )
    (net (code "125") (name "unconnected-(C30-PadV2)") (class "Default")
      (node (ref "C30") (pin "V2") (pinfunction "V2_V2") (pintype "output"))
    )
  )
)
